# COMMUNICATION.net
KiCad netlist of a schematic drawn in Altium Designer
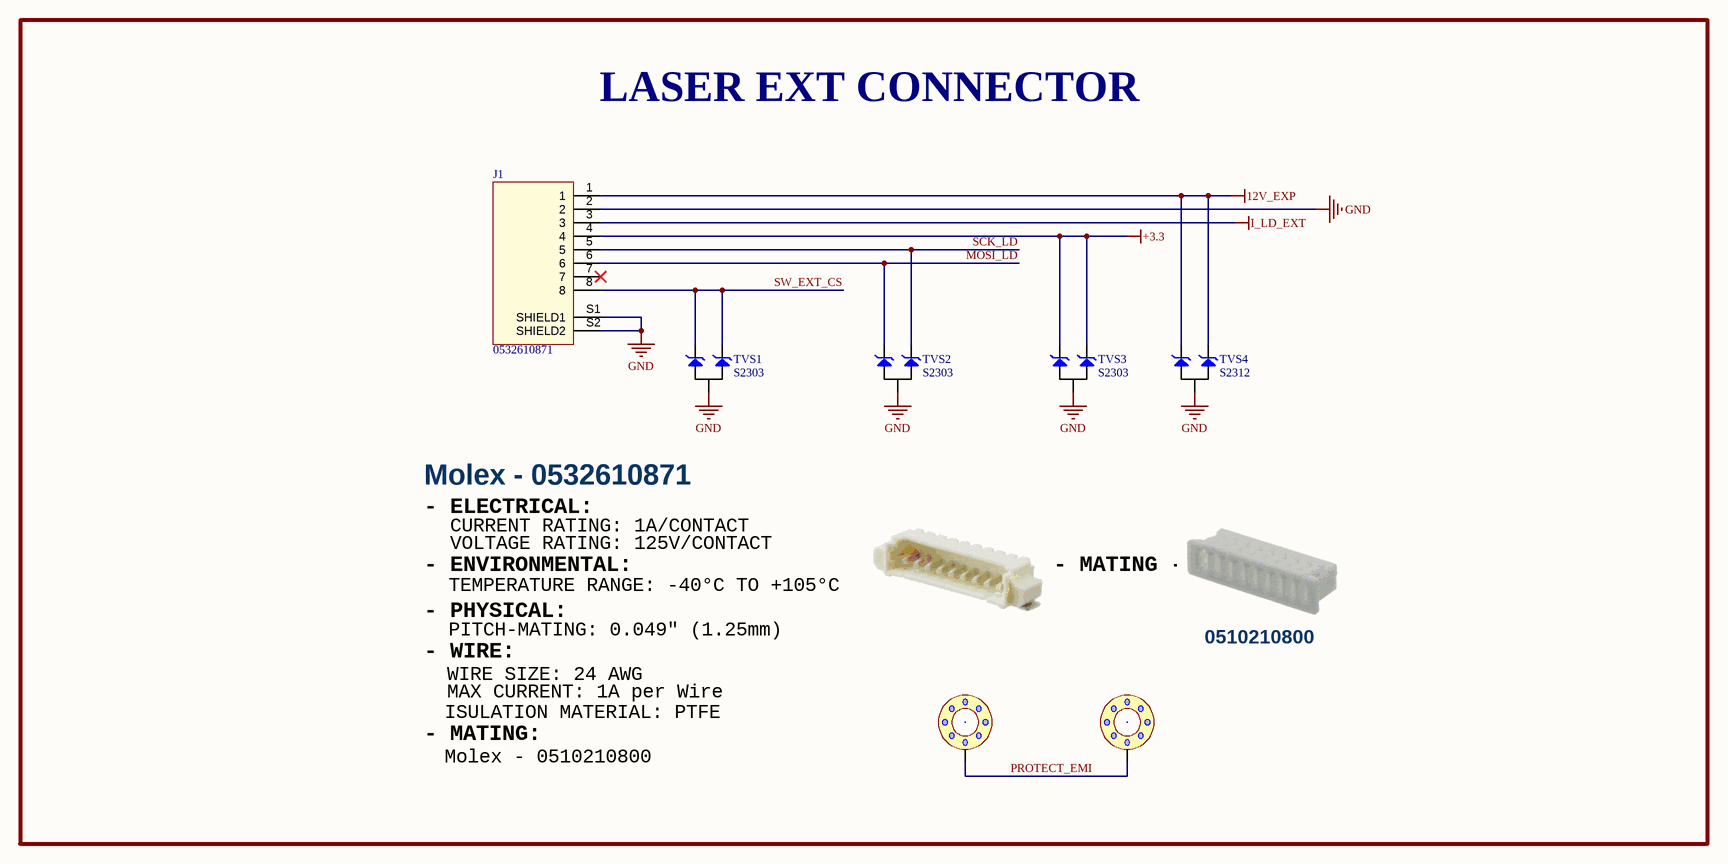
[diagram p0: COMMUNICATION.SchDoc]

(export (version "E")
  (design (tool "Eeschema 10.0.6"))
  (components
    (comp (ref "Hole1")
      (value "Hole")
      (footprint "Hole space")
      (libsource (lib "SATELLITE_4U_LASER_EXT_1.4.0") (part "Hole"))
    )
    (comp (ref "Hole2")
      (value "Hole")
      (footprint "Hole space")
      (libsource (lib "SATELLITE_4U_LASER_EXT_1.4.0") (part "Hole"))
    )
    (comp (ref "J1")
      (value "0532610871")
      (footprint "0532610871")
      (description "CONN HEADER SMD R/A 8POS 1.25MM")
      (libsource (lib "SATELLITE_4U_LASER_EXT_1.4.0") (part "Header8 - Shield"))
    )
    (comp (ref "TVS1")
      (value "S2303")
      (footprint "SOT23-123")
      (description "TVS DIODE 3.3VWM 8VC SOT233")
      (libsource (lib "SATELLITE_4U_LASER_EXT_1.4.0") (part "S2303"))
    )
    (comp (ref "TVS2")
      (value "S2303")
      (footprint "SOT23-123")
      (description "TVS DIODE 3.3VWM 8VC SOT233")
      (libsource (lib "SATELLITE_4U_LASER_EXT_1.4.0") (part "S2303"))
    )
    (comp (ref "TVS3")
      (value "S2303")
      (footprint "SOT23-123")
      (description "TVS DIODE 3.3VWM 8VC SOT233")
      (libsource (lib "SATELLITE_4U_LASER_EXT_1.4.0") (part "S2303"))
    )
    (comp (ref "TVS4")
      (value "S2312")
      (footprint "SOT23-123")
      (description "TVS DIODE 12VWM 19VC SOT233")
      (libsource (lib "SATELLITE_4U_LASER_EXT_1.4.0") (part "S2315"))
    )
  )
  (nets
    (net (code "1") (name "+3.3") (class "Default")
      (node (ref "J1") (pin "4") (pinfunction "4_4") (pintype "passive"))
      (node (ref "TVS3") (pin "1") (pintype "passive"))
      (node (ref "TVS3") (pin "3") (pintype "passive"))
    )
    (net (code "2") (name "/MOSI_LD") (class "Default")
      (node (ref "J1") (pin "6") (pinfunction "6_6") (pintype "passive"))
      (node (ref "TVS2") (pin "3") (pintype "passive"))
    )
    (net (code "3") (name "/PROTECT_EMI") (class "Default")
      (node (ref "Hole1") (pin "1") (pinfunction "1_1") (pintype "passive"))
      (node (ref "Hole2") (pin "1") (pinfunction "1_1") (pintype "passive"))
    )
    (net (code "4") (name "/SCK_LD") (class "Default")
      (node (ref "J1") (pin "5") (pinfunction "5_5") (pintype "passive"))
      (node (ref "TVS2") (pin "1") (pintype "passive"))
    )
    (net (code "5") (name "/SW_EXT_CS") (class "Default")
      (node (ref "J1") (pin "8") (pinfunction "8_8") (pintype "passive"))
      (node (ref "TVS1") (pin "1") (pintype "passive"))
      (node (ref "TVS1") (pin "3") (pintype "passive"))
    )
    (net (code "6") (name "12V_EXP") (class "Default")
      (node (ref "J1") (pin "1") (pinfunction "1_1") (pintype "passive"))
      (node (ref "TVS4") (pin "1") (pintype "passive"))
      (node (ref "TVS4") (pin "3") (pintype "passive"))
    )
    (net (code "7") (name "GND") (class "Default")
      (node (ref "J1") (pin "2") (pinfunction "2_2") (pintype "passive"))
      (node (ref "J1") (pin "S1") (pinfunction "SHIELD1_S1") (pintype "passive"))
      (node (ref "J1") (pin "S2") (pinfunction "SHIELD2_S2") (pintype "passive"))
      (node (ref "TVS1") (pin "2") (pintype "passive"))
      (node (ref "TVS2") (pin "2") (pintype "passive"))
      (node (ref "TVS3") (pin "2") (pintype "passive"))
      (node (ref "TVS4") (pin "2") (pintype "passive"))
    )
    (net (code "8") (name "I_LD_EXT") (class "Default")
      (node (ref "J1") (pin "3") (pinfunction "3_3") (pintype "passive"))
    )
    (net (code "9") (name "unconnected-(J1-Pad7)") (class "Default")
      (node (ref "J1") (pin "7") (pinfunction "7_7") (pintype "passive+no_connect"))
    )
  )
)
